# LM_HTR_001.net
KiCad netlist of a schematic drawn in Altium Designer
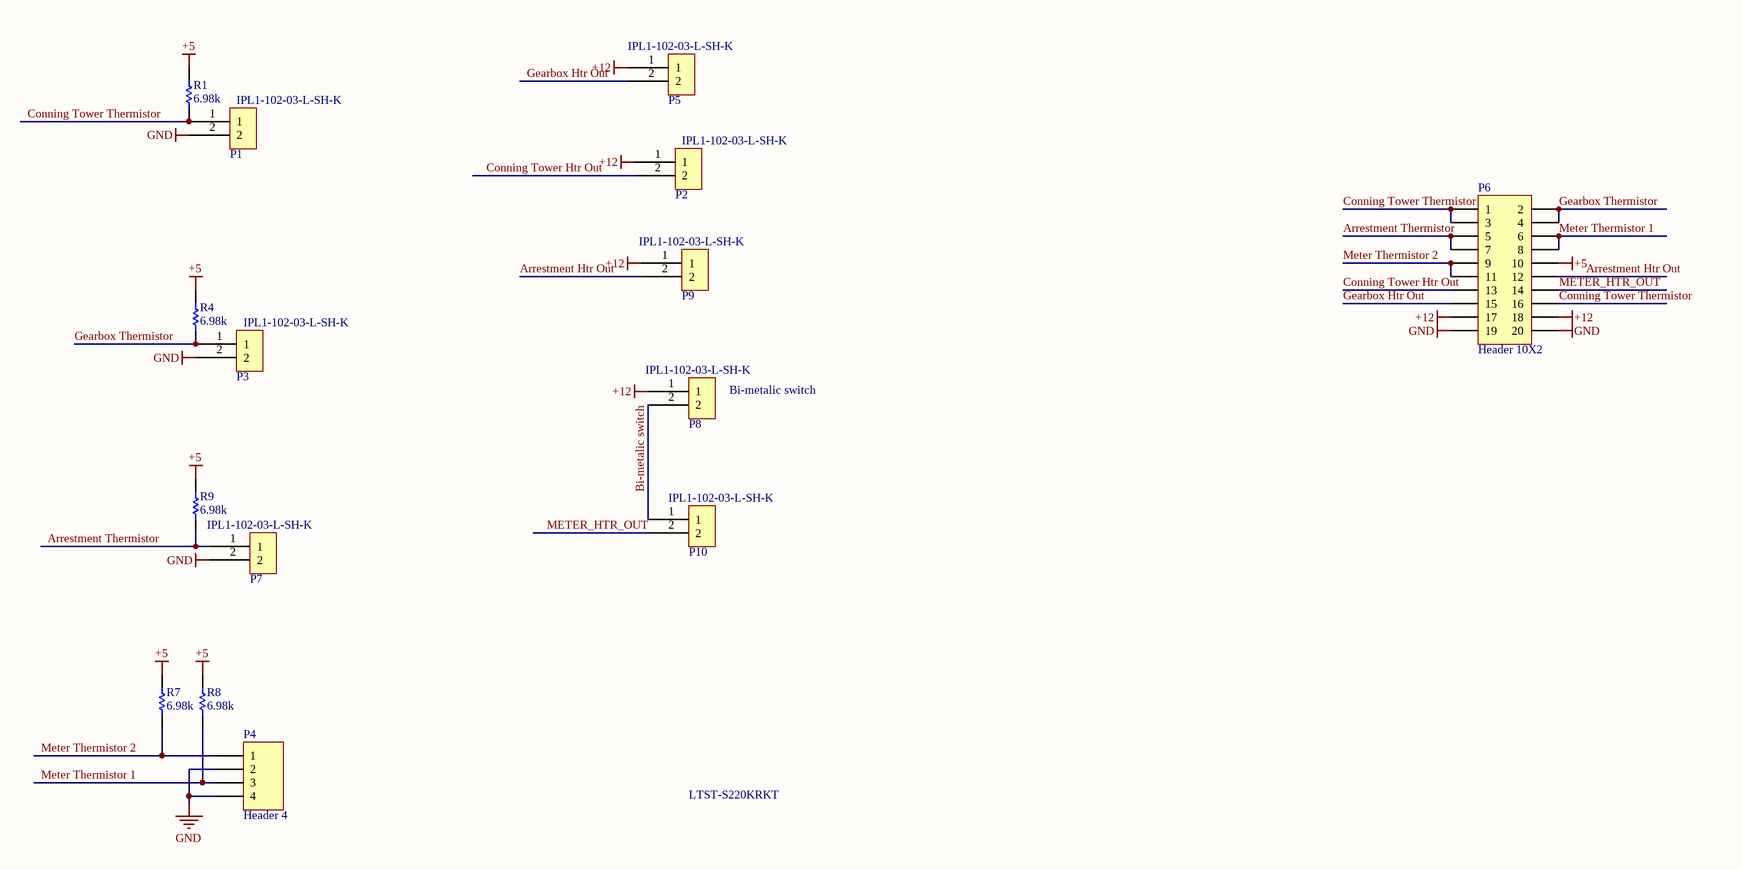
[diagram p0: LM_HTR_001.SchDoc]

(export (version "E")
  (design (tool "Eeschema 10.0.6"))
  (components
    (comp (ref "P1")
      (value "IPL1-102-03-L-SH-K")
      (footprint "IPL1-102-03-L-SH-K")
      (fields
        (field (name "SUPPLIER PART NUMBER 1") "IPL1-102-03-L-SH-K")
        (field (name "MANUFACTURER") "Samtec")
      )
      (libsource (lib "ZLS_Schematic_lib") (part "IPL1-102-03-L-SH-K"))
    )
    (comp (ref "P2")
      (value "IPL1-102-03-L-SH-K")
      (footprint "IPL1-102-03-L-SH-K")
      (fields
        (field (name "SUPPLIER PART NUMBER 1") "IPL1-102-03-L-SH-K")
        (field (name "MANUFACTURER") "Samtec")
      )
      (libsource (lib "ZLS_Schematic_lib") (part "IPL1-102-03-L-SH-K"))
    )
    (comp (ref "P3")
      (value "IPL1-102-03-L-SH-K")
      (footprint "IPL1-102-03-L-SH-K")
      (fields
        (field (name "SUPPLIER PART NUMBER 1") "IPL1-102-03-L-SH-K")
        (field (name "MANUFACTURER") "Samtec")
      )
      (libsource (lib "ZLS_Schematic_lib") (part "IPL1-102-03-L-SH-K"))
    )
    (comp (ref "P4")
      (value "Header 4")
      (footprint "IPL1-104-01-L-S-K")
      (description "Header, 4-Pin")
      (fields (field (name "PUBLISHER") "Altium Limited"))
      (libsource (lib "Miscellaneous Connectors") (part "Header 4"))
    )
    (comp (ref "P5")
      (value "IPL1-102-03-L-SH-K")
      (footprint "IPL1-102-03-L-SH-K")
      (fields
        (field (name "SUPPLIER PART NUMBER 1") "IPL1-102-03-L-SH-K")
        (field (name "MANUFACTURER") "Samtec")
      )
      (libsource (lib "ZLS_Schematic_lib") (part "IPL1-102-03-L-SH-K"))
    )
    (comp (ref "P6")
      (value "Header 10X2")
      (footprint "IPL1-110-01-L-D-RE1-K")
      (description "Header, 10-Pin, Dual row")
      (fields (field (name "PUBLISHER") "Altium Limited"))
      (libsource (lib "Miscellaneous Connectors") (part "Header 10X2"))
    )
    (comp (ref "P7")
      (value "IPL1-102-03-L-SH-K")
      (footprint "IPL1-102-01-L-S-RE1-K")
      (fields
        (field (name "SUPPLIER PART NUMBER 1") "IPL1-102-03-L-SH-K")
        (field (name "MANUFACTURER") "Samtec")
      )
      (libsource (lib "ZLS_Schematic_lib") (part "IPL1-102-03-L-SH-K"))
    )
    (comp (ref "P8")
      (value "IPL1-102-03-L-SH-K")
      (footprint "IPL1-102-03-L-SH-K")
      (fields
        (field (name "SUPPLIER PART NUMBER 1") "IPL1-102-03-L-SH-K")
        (field (name "MANUFACTURER") "Samtec")
      )
      (libsource (lib "ZLS_Schematic_lib") (part "IPL1-102-03-L-SH-K"))
    )
    (comp (ref "P9")
      (value "IPL1-102-03-L-SH-K")
      (footprint "IPL1-102-03-L-SH-K")
      (fields
        (field (name "SUPPLIER PART NUMBER 1") "IPL1-102-03-L-SH-K")
        (field (name "MANUFACTURER") "Samtec")
      )
      (libsource (lib "ZLS_Schematic_lib") (part "IPL1-102-03-L-SH-K"))
    )
    (comp (ref "P10")
      (value "IPL1-102-03-L-SH-K")
      (footprint "IPL1-102-03-L-SH-K")
      (fields
        (field (name "SUPPLIER PART NUMBER 1") "IPL1-102-03-L-SH-K")
        (field (name "MANUFACTURER") "Samtec")
      )
      (libsource (lib "ZLS_Schematic_lib") (part "IPL1-102-03-L-SH-K"))
    )
    (comp (ref "R1")
      (value "6K98 1% 0805(2012)")
      (footprint "RESC0805(2012)_N")
      (description "6K98 0.125W 1% 0805 (2012 Metric)  SMD")
      (fields
        (field (name "MANUFACTURER") "Vishay Dale")
        (field (name "MANUFACTURER PART NUMBER") "CRCW08056K98FKEA")
        (field (name "RESISTANCE (OHMS)") "6.98k")
      )
      (libsource (lib "Altium Content Vault") (part "CMP-1013-00606-1"))
    )
    (comp (ref "R4")
      (value "6K98 1% 0805(2012)")
      (footprint "RESC0805(2012)_N")
      (description "6K98 0.125W 1% 0805 (2012 Metric)  SMD")
      (fields
        (field (name "MANUFACTURER") "Vishay Dale")
        (field (name "MANUFACTURER PART NUMBER") "CRCW08056K98FKEA")
        (field (name "RESISTANCE (OHMS)") "6.98k")
      )
      (libsource (lib "Altium Content Vault") (part "CMP-1013-00606-1"))
    )
    (comp (ref "R7")
      (value "6K98 1% 0805(2012)")
      (footprint "RESC0805(2012)_N")
      (description "6K98 0.125W 1% 0805 (2012 Metric)  SMD")
      (fields
        (field (name "MANUFACTURER") "Vishay Dale")
        (field (name "MANUFACTURER PART NUMBER") "CRCW08056K98FKEA")
        (field (name "RESISTANCE (OHMS)") "6.98k")
      )
      (libsource (lib "Altium Content Vault") (part "CMP-1013-00606-1"))
    )
    (comp (ref "R8")
      (value "6K98 1% 0805(2012)")
      (footprint "RESC0805(2012)_N")
      (description "6K98 0.125W 1% 0805 (2012 Metric)  SMD")
      (fields
        (field (name "MANUFACTURER") "Vishay Dale")
        (field (name "MANUFACTURER PART NUMBER") "CRCW08056K98FKEA")
        (field (name "RESISTANCE (OHMS)") "6.98k")
      )
      (libsource (lib "Altium Content Vault") (part "CMP-1013-00606-1"))
    )
    (comp (ref "R9")
      (value "6K98 1% 0805(2012)")
      (footprint "RESC0805(2012)_N")
      (description "6K98 0.125W 1% 0805 (2012 Metric)  SMD")
      (fields
        (field (name "MANUFACTURER") "Vishay Dale")
        (field (name "MANUFACTURER PART NUMBER") "CRCW08056K98FKEA")
        (field (name "RESISTANCE (OHMS)") "6.98k")
      )
      (libsource (lib "Altium Content Vault") (part "CMP-1013-00606-1"))
    )
  )
  (nets
    (net (code "1") (name "+5") (class "Default")
      (node (ref "P6") (pin "10") (pinfunction "10_10") (pintype "passive"))
      (node (ref "R1") (pin "2") (pinfunction "2_2") (pintype "passive"))
      (node (ref "R4") (pin "2") (pinfunction "2_2") (pintype "passive"))
      (node (ref "R7") (pin "1") (pinfunction "1_1") (pintype "passive"))
      (node (ref "R8") (pin "2") (pinfunction "2_2") (pintype "passive"))
      (node (ref "R9") (pin "1") (pinfunction "1_1") (pintype "passive"))
    )
    (net (code "2") (name "+12") (class "Default")
      (node (ref "P2") (pin "1") (pinfunction "1_1") (pintype "passive"))
      (node (ref "P5") (pin "1") (pinfunction "1_1") (pintype "passive"))
      (node (ref "P6") (pin "17") (pinfunction "17_17") (pintype "passive"))
      (node (ref "P6") (pin "18") (pinfunction "18_18") (pintype "passive"))
      (node (ref "P8") (pin "1") (pinfunction "1_1") (pintype "passive"))
      (node (ref "P9") (pin "1") (pinfunction "1_1") (pintype "passive"))
    )
    (net (code "3") (name "/Arrestment Htr Out") (class "Default")
      (node (ref "P6") (pin "12") (pinfunction "12_12") (pintype "passive"))
      (node (ref "P9") (pin "2") (pinfunction "2_2") (pintype "passive"))
    )
    (net (code "4") (name "/Arrestment Thermistor") (class "Default")
      (node (ref "P6") (pin "5") (pinfunction "5_5") (pintype "passive"))
      (node (ref "P6") (pin "7") (pinfunction "7_7") (pintype "passive"))
      (node (ref "P7") (pin "1") (pinfunction "1_1") (pintype "passive"))
      (node (ref "R9") (pin "2") (pinfunction "2_2") (pintype "passive"))
    )
    (net (code "5") (name "/Bi-metalic switch") (class "Default")
      (node (ref "P10") (pin "1") (pinfunction "1_1") (pintype "passive"))
      (node (ref "P8") (pin "2") (pinfunction "2_2") (pintype "passive"))
    )
    (net (code "6") (name "/Conning Tower Htr Out") (class "Default")
      (node (ref "P2") (pin "2") (pinfunction "2_2") (pintype "passive"))
      (node (ref "P6") (pin "13") (pinfunction "13_13") (pintype "passive"))
    )
    (net (code "7") (name "/Conning Tower Thermistor") (class "Default")
      (node (ref "P1") (pin "1") (pinfunction "1_1") (pintype "passive"))
      (node (ref "P6") (pin "1") (pinfunction "1_1") (pintype "passive"))
      (node (ref "P6") (pin "16") (pinfunction "16_16") (pintype "passive"))
      (node (ref "P6") (pin "3") (pinfunction "3_3") (pintype "passive"))
      (node (ref "R1") (pin "1") (pinfunction "1_1") (pintype "passive"))
    )
    (net (code "8") (name "/Gearbox Htr Out") (class "Default")
      (node (ref "P5") (pin "2") (pinfunction "2_2") (pintype "passive"))
      (node (ref "P6") (pin "15") (pinfunction "15_15") (pintype "passive"))
    )
    (net (code "9") (name "/Gearbox Thermistor") (class "Default")
      (node (ref "P3") (pin "1") (pinfunction "1_1") (pintype "passive"))
      (node (ref "P6") (pin "2") (pinfunction "2_2") (pintype "passive"))
      (node (ref "P6") (pin "4") (pinfunction "4_4") (pintype "passive"))
      (node (ref "R4") (pin "1") (pinfunction "1_1") (pintype "passive"))
    )
    (net (code "10") (name "/METER_HTR_OUT") (class "Default")
      (node (ref "P10") (pin "2") (pinfunction "2_2") (pintype "passive"))
      (node (ref "P6") (pin "14") (pinfunction "14_14") (pintype "passive"))
    )
    (net (code "11") (name "/Meter Thermistor 1") (class "Default")
      (node (ref "P4") (pin "3") (pinfunction "3_3") (pintype "passive"))
      (node (ref "P6") (pin "6") (pinfunction "6_6") (pintype "passive"))
      (node (ref "P6") (pin "8") (pinfunction "8_8") (pintype "passive"))
      (node (ref "R8") (pin "1") (pinfunction "1_1") (pintype "passive"))
    )
    (net (code "12") (name "/Meter Thermistor 2") (class "Default")
      (node (ref "P4") (pin "1") (pinfunction "1_1") (pintype "passive"))
      (node (ref "P6") (pin "11") (pinfunction "11_11") (pintype "passive"))
      (node (ref "P6") (pin "9") (pinfunction "9_9") (pintype "passive"))
      (node (ref "R7") (pin "2") (pinfunction "2_2") (pintype "passive"))
    )
    (net (code "13") (name "GND") (class "Default")
      (node (ref "P1") (pin "2") (pinfunction "2_2") (pintype "passive"))
      (node (ref "P3") (pin "2") (pinfunction "2_2") (pintype "passive"))
      (node (ref "P4") (pin "2") (pinfunction "2_2") (pintype "passive"))
      (node (ref "P4") (pin "4") (pinfunction "4_4") (pintype "passive"))
      (node (ref "P6") (pin "19") (pinfunction "19_19") (pintype "passive"))
      (node (ref "P6") (pin "20") (pinfunction "20_20") (pintype "passive"))
      (node (ref "P7") (pin "2") (pinfunction "2_2") (pintype "passive"))
    )
  )
)
